# RTC.net
KiCad netlist of a schematic drawn in Altium Designer
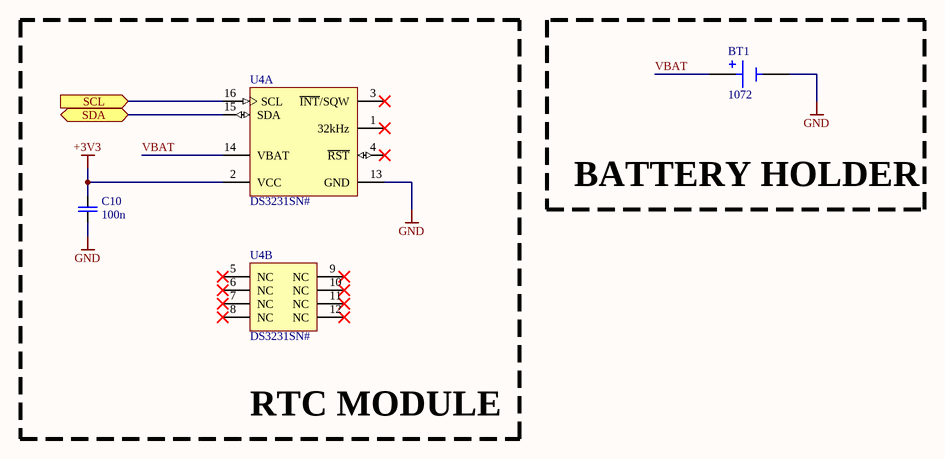
[diagram p0: RTC.SchDoc]

(export (version "E")
  (design (tool "Eeschema 10.0.6"))
  (components
    (comp (ref "BT1")
      (value "1072")
      (footprint "BAT_1072")
      (description "Battery Holder CR1220/1225")
      (fields (field (name "MF") "Keystone Electronics"))
      (libsource (lib "1072") (part "1072"))
    )
    (comp (ref "C10")
      (value "100n")
      (footprint "C0603")
      (description "Generic 0603 SMD Ceramic Capacitor")
      (libsource (lib "PolSl Racing - Electrical") (part "Capacitor"))
    )
    (comp (ref "U4")
      (value "DS3231SN#")
      (footprint "W16#H2_L")
      (libsource (lib "Altium Content Vault") (part "MAX-RTC-16-DS3231S-W16#H2"))
    )
  )
  (nets
    (net (code "1") (name "+3V3") (class "Default")
      (node (ref "C10") (pin "2") (pinfunction "2_2") (pintype "passive"))
      (node (ref "U4") (pin "2") (pinfunction "VCC_2") (pintype "power_in"))
    )
    (net (code "2") (name "/SCL") (class "Default")
      (node (ref "U4") (pin "16") (pinfunction "SCL_16") (pintype "input"))
    )
    (net (code "3") (name "/SDA") (class "Default")
      (node (ref "U4") (pin "15") (pinfunction "SDA_15") (pintype "bidirectional"))
    )
    (net (code "4") (name "/VBAT") (class "Default")
      (node (ref "BT1") (pin "P") (pinfunction "POS_P") (pintype "passive"))
      (node (ref "U4") (pin "14") (pinfunction "VBAT_14") (pintype "power_in"))
    )
    (net (code "5") (name "GND") (class "Default")
      (node (ref "BT1") (pin "N") (pinfunction "NEG_N") (pintype "passive"))
      (node (ref "C10") (pin "1") (pinfunction "1_1") (pintype "passive"))
      (node (ref "U4") (pin "13") (pinfunction "GND_13") (pintype "power_in"))
    )
    (net (code "6") (name "unconnected-(U4A-32kHz-Pad1)") (class "Default")
      (node (ref "U4") (pin "1") (pinfunction "32kHz_1") (pintype "open_collector+no_connect"))
    )
    (net (code "7") (name "unconnected-(U4A-~{INT}{slash}SQW-Pad3)") (class "Default")
      (node (ref "U4") (pin "3") (pinfunction "~{INT}/SQW_3") (pintype "open_collector+no_connect"))
    )
    (net (code "8") (name "unconnected-(U4A-~{RST}-Pad4)") (class "Default")
      (node (ref "U4") (pin "4") (pinfunction "~{RST}_4") (pintype "bidirectional+no_connect"))
    )
    (net (code "9") (name "unconnected-(U4B-NC-Pad5)") (class "Default")
      (node (ref "U4") (pin "5") (pinfunction "NC_5") (pintype "passive+no_connect"))
    )
    (net (code "10") (name "unconnected-(U4B-NC-Pad6)") (class "Default")
      (node (ref "U4") (pin "6") (pinfunction "NC_6") (pintype "passive+no_connect"))
    )
    (net (code "11") (name "unconnected-(U4B-NC-Pad7)") (class "Default")
      (node (ref "U4") (pin "7") (pinfunction "NC_7") (pintype "passive+no_connect"))
    )
    (net (code "12") (name "unconnected-(U4B-NC-Pad8)") (class "Default")
      (node (ref "U4") (pin "8") (pinfunction "NC_8") (pintype "passive+no_connect"))
    )
    (net (code "13") (name "unconnected-(U4B-NC-Pad9)") (class "Default")
      (node (ref "U4") (pin "9") (pinfunction "NC_9") (pintype "passive+no_connect"))
    )
    (net (code "14") (name "unconnected-(U4B-NC-Pad10)") (class "Default")
      (node (ref "U4") (pin "10") (pinfunction "NC_10") (pintype "passive+no_connect"))
    )
    (net (code "15") (name "unconnected-(U4B-NC-Pad11)") (class "Default")
      (node (ref "U4") (pin "11") (pinfunction "NC_11") (pintype "passive+no_connect"))
    )
    (net (code "16") (name "unconnected-(U4B-NC-Pad12)") (class "Default")
      (node (ref "U4") (pin "12") (pinfunction "NC_12") (pintype "passive+no_connect"))
    )
  )
)
